# EasyEDA_SCH_alexo_2026-07-04.net
KiCad netlist of a schematic drawn in EasyEDA
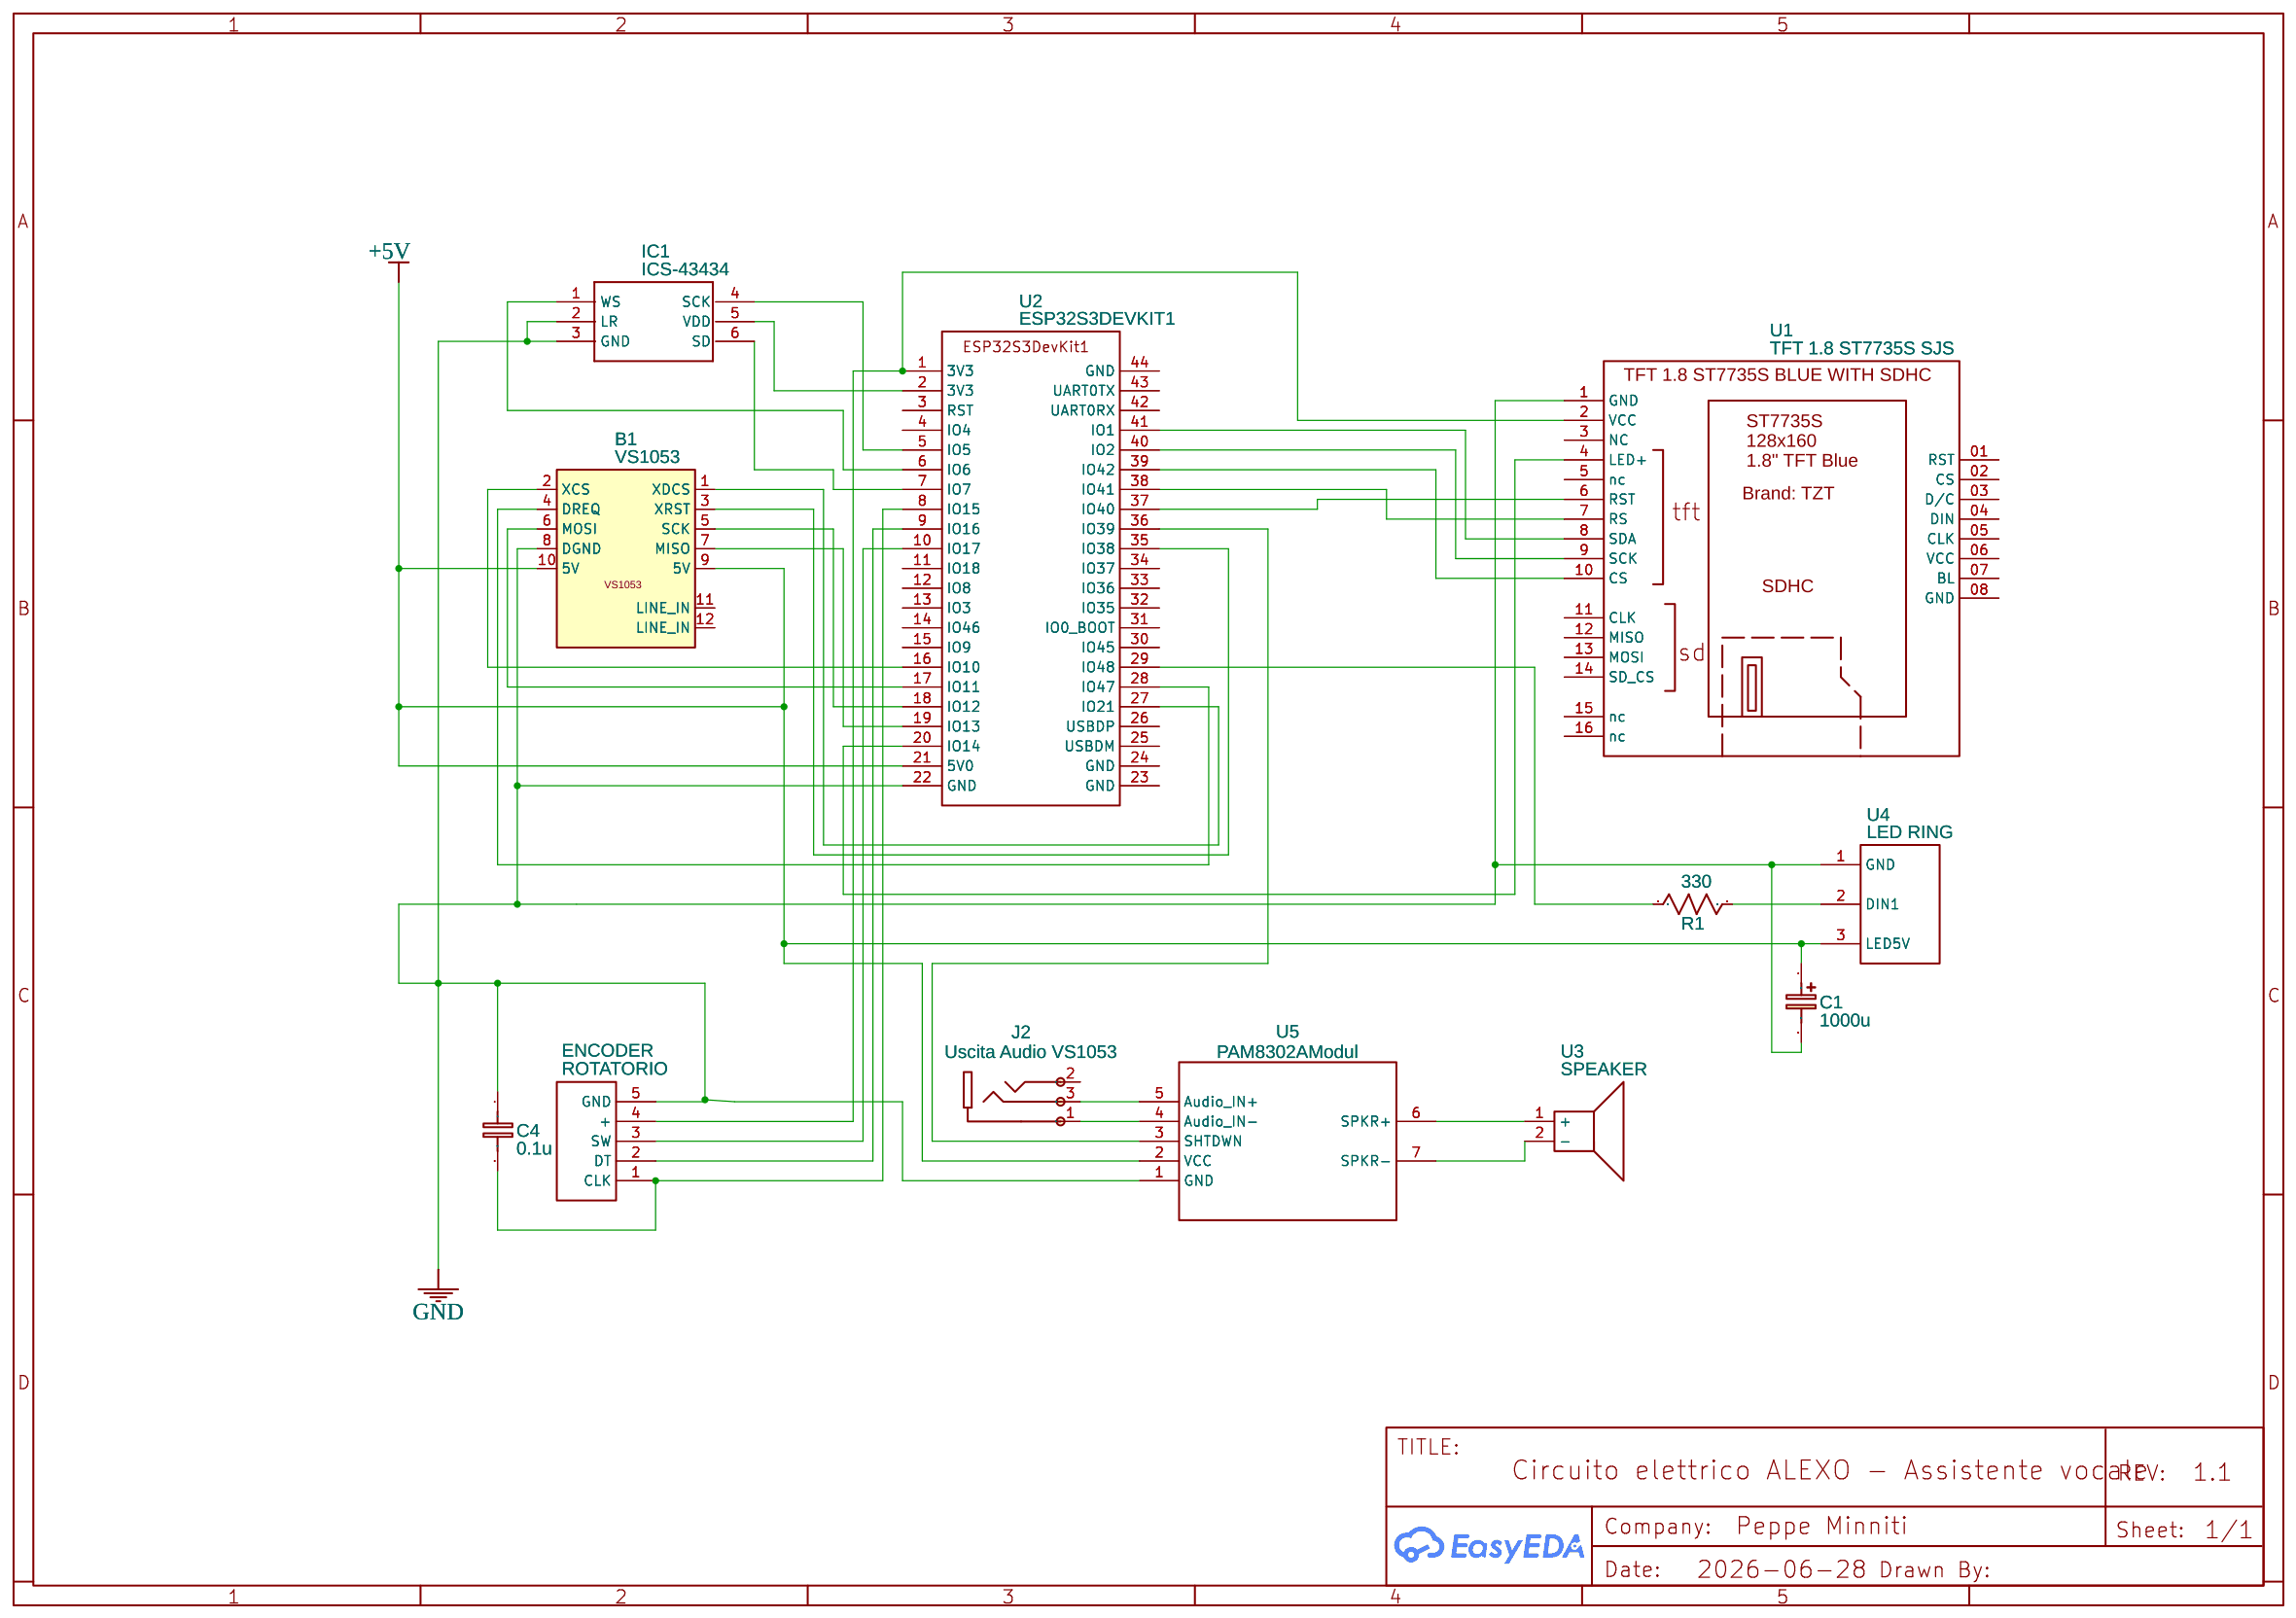
[diagram p0: schematic sheet]

(export (version "E")
  (design (tool "Eeschema 10.0.6"))
  (components
    (comp (ref "B1") (value "VS1053") (libsource (lib "") (part "VS1053")))
    (comp (ref "C1") (value "1000u") (libsource (lib "") (part "C_Tan_SMD_A_EU")))
    (comp (ref "C4") (value "0.1u") (libsource (lib "") (part "C_0603_EU")))
    (comp (ref "ENCODER") (value "ROTATORIO") (libsource (lib "") (part "ROTARY ENCODER (BREAKOUT)")))
    (comp (ref "IC1") (value "ICS-43434") (libsource (lib "") (part "ICS-43434")))
    (comp (ref "J2")
      (value "Uscita Audio VS1053")
      (fields (field (name "Manufacturer Part") "320B/PJ-0013.5Jacks"))
      (libsource (lib "") (part "320B/PJ-0013.5JACKS"))
    )
    (comp (ref "R1") (value "330") (libsource (lib "") (part "R_0603_US")))
    (comp (ref "U1") (value "TFT 1.8 ST7735S SJS") (libsource (lib "") (part "TFT 1.8 ST7735S SJS")))
    (comp (ref "U2")
      (value "ESP32S3DEVKIT1")
      (fields (field (name "Manufacturer Part") "ESP32S3DevKit1"))
      (libsource (lib "") (part "ESP32S3DEVKIT1 COPY"))
    )
    (comp (ref "U3") (value "SPEAKER") (libsource (lib "") (part "SPEAKER COPY")))
    (comp (ref "U4") (value "LED RING") (libsource (lib "") (part "LED RING")))
    (comp (ref "U5") (value "PAM8302AModul") (libsource (lib "") (part "PAM8302AModul")))
  )
  (nets
    (net (code "1") (name "+5V") (class "Default")
      (node (ref "B1") (pin "10") (pinfunction "5V_10") (pintype "bidirectional"))
      (node (ref "B1") (pin "9") (pinfunction "5V_9") (pintype "bidirectional"))
      (node (ref "C1") (pin "1") (pinfunction "1_1") (pintype "unspecified"))
      (node (ref "U2") (pin "21") (pinfunction "5V0_21") (pintype "unspecified"))
      (node (ref "U4") (pin "3") (pinfunction "LED5V_3") (pintype "unspecified"))
      (node (ref "U5") (pin "2") (pinfunction "VCC_2") (pintype "unspecified"))
    )
    (net (code "2") (name "GND") (class "Default")
      (node (ref "B1") (pin "8") (pinfunction "DGND_8") (pintype "bidirectional"))
      (node (ref "C1") (pin "2") (pinfunction "2_2") (pintype "unspecified"))
      (node (ref "C4") (pin "1") (pinfunction "1_1") (pintype "unspecified"))
      (node (ref "ENCODER") (pin "5") (pinfunction "GND_5") (pintype "unspecified"))
      (node (ref "IC1") (pin "2") (pinfunction "LR_2") (pintype "bidirectional"))
      (node (ref "IC1") (pin "3") (pinfunction "GND_3") (pintype "bidirectional"))
      (node (ref "U1") (pin "1") (pinfunction "GND_1") (pintype "unspecified"))
      (node (ref "U2") (pin "22") (pinfunction "GND_22") (pintype "unspecified"))
      (node (ref "U4") (pin "1") (pinfunction "GND_1") (pintype "unspecified"))
      (node (ref "U5") (pin "1") (pinfunction "GND_1") (pintype "unspecified"))
    )
    (net (code "3") (name "Net-(B1-DREQ)") (class "Default")
      (node (ref "B1") (pin "4") (pinfunction "DREQ_4") (pintype "bidirectional"))
      (node (ref "U2") (pin "28") (pinfunction "IO47_28") (pintype "unspecified"))
    )
    (net (code "4") (name "Net-(B1-MISO)") (class "Default")
      (node (ref "B1") (pin "7") (pinfunction "MISO_7") (pintype "bidirectional"))
      (node (ref "U2") (pin "19") (pinfunction "IO13_19") (pintype "unspecified"))
    )
    (net (code "5") (name "Net-(B1-MOSI)") (class "Default")
      (node (ref "B1") (pin "6") (pinfunction "MOSI_6") (pintype "bidirectional"))
      (node (ref "U2") (pin "17") (pinfunction "IO11_17") (pintype "unspecified"))
    )
    (net (code "6") (name "Net-(B1-SCK)") (class "Default")
      (node (ref "B1") (pin "5") (pinfunction "SCK_5") (pintype "bidirectional"))
      (node (ref "U2") (pin "18") (pinfunction "IO12_18") (pintype "unspecified"))
    )
    (net (code "7") (name "Net-(B1-XCS)") (class "Default")
      (node (ref "B1") (pin "2") (pinfunction "XCS_2") (pintype "bidirectional"))
      (node (ref "U2") (pin "16") (pinfunction "IO10_16") (pintype "unspecified"))
    )
    (net (code "8") (name "Net-(B1-XDCS)") (class "Default")
      (node (ref "B1") (pin "1") (pinfunction "XDCS_1") (pintype "bidirectional"))
      (node (ref "U2") (pin "27") (pinfunction "IO21_27") (pintype "unspecified"))
    )
    (net (code "9") (name "Net-(B1-XRST)") (class "Default")
      (node (ref "B1") (pin "3") (pinfunction "XRST_3") (pintype "bidirectional"))
      (node (ref "U2") (pin "35") (pinfunction "IO38_35") (pintype "unspecified"))
    )
    (net (code "10") (name "Net-(ENCODER-+)") (class "Default")
      (node (ref "ENCODER") (pin "4") (pinfunction "+_4") (pintype "unspecified"))
      (node (ref "U1") (pin "2") (pinfunction "VCC_2") (pintype "unspecified"))
      (node (ref "U2") (pin "1") (pinfunction "3V3_1") (pintype "unspecified"))
    )
    (net (code "11") (name "Net-(ENCODER-CLK)") (class "Default")
      (node (ref "C4") (pin "2") (pinfunction "2_2") (pintype "unspecified"))
      (node (ref "ENCODER") (pin "1") (pinfunction "CLK_1") (pintype "unspecified"))
      (node (ref "U2") (pin "8") (pinfunction "IO15_8") (pintype "unspecified"))
    )
    (net (code "12") (name "Net-(ENCODER-DT)") (class "Default")
      (node (ref "ENCODER") (pin "2") (pinfunction "DT_2") (pintype "unspecified"))
      (node (ref "U2") (pin "9") (pinfunction "IO16_9") (pintype "unspecified"))
    )
    (net (code "13") (name "Net-(ENCODER-SW)") (class "Default")
      (node (ref "ENCODER") (pin "3") (pinfunction "SW_3") (pintype "unspecified"))
      (node (ref "U2") (pin "10") (pinfunction "IO17_10") (pintype "unspecified"))
    )
    (net (code "14") (name "Net-(IC1-SCK)") (class "Default")
      (node (ref "IC1") (pin "4") (pinfunction "SCK_4") (pintype "bidirectional"))
      (node (ref "U2") (pin "5") (pinfunction "IO5_5") (pintype "unspecified"))
    )
    (net (code "15") (name "Net-(IC1-SD)") (class "Default")
      (node (ref "IC1") (pin "6") (pinfunction "SD_6") (pintype "bidirectional"))
      (node (ref "U2") (pin "7") (pinfunction "IO7_7") (pintype "unspecified"))
    )
    (net (code "16") (name "Net-(IC1-VDD)") (class "Default")
      (node (ref "IC1") (pin "5") (pinfunction "VDD_5") (pintype "bidirectional"))
      (node (ref "U2") (pin "2") (pinfunction "3V3_2") (pintype "unspecified"))
    )
    (net (code "17") (name "Net-(IC1-WS)") (class "Default")
      (node (ref "IC1") (pin "1") (pinfunction "WS_1") (pintype "bidirectional"))
      (node (ref "U2") (pin "6") (pinfunction "IO6_6") (pintype "unspecified"))
    )
    (net (code "18") (name "Net-(U1-LED+)") (class "Default")
      (node (ref "U1") (pin "4") (pinfunction "LED+_4") (pintype "unspecified"))
      (node (ref "U2") (pin "20") (pinfunction "IO14_20") (pintype "unspecified"))
    )
    (net (code "19") (name "Net-(U1-RS)") (class "Default")
      (node (ref "U1") (pin "7") (pinfunction "RS_7") (pintype "unspecified"))
      (node (ref "U2") (pin "38") (pinfunction "IO41_38") (pintype "unspecified"))
    )
    (net (code "20") (name "Net-(U1-SCK)") (class "Default")
      (node (ref "U1") (pin "9") (pinfunction "SCK_9") (pintype "unspecified"))
      (node (ref "U2") (pin "40") (pinfunction "IO2_40") (pintype "unspecified"))
    )
    (net (code "21") (name "Net-(U1-SDA)") (class "Default")
      (node (ref "U1") (pin "8") (pinfunction "SDA_8") (pintype "unspecified"))
      (node (ref "U2") (pin "41") (pinfunction "IO1_41") (pintype "unspecified"))
    )
    (net (code "22") (name "Net-(U2-IO39)") (class "Default")
      (node (ref "U2") (pin "36") (pinfunction "IO39_36") (pintype "unspecified"))
      (node (ref "U5") (pin "3") (pinfunction "SHTDWN_3") (pintype "unspecified"))
    )
    (net (code "23") (name "Net-(U2-IO40)") (class "Default")
      (node (ref "U1") (pin "6") (pinfunction "RST_6") (pintype "unspecified"))
      (node (ref "U2") (pin "37") (pinfunction "IO40_37") (pintype "unspecified"))
    )
    (net (code "24") (name "Net-(U2-IO42)") (class "Default")
      (node (ref "U1") (pin "10") (pinfunction "CS_10") (pintype "unspecified"))
      (node (ref "U2") (pin "39") (pinfunction "IO42_39") (pintype "unspecified"))
    )
    (net (code "25") (name "Net-(U2-IO48)") (class "Default")
      (node (ref "R1") (pin "1") (pinfunction "1_1") (pintype "unspecified"))
      (node (ref "U2") (pin "29") (pinfunction "IO48_29") (pintype "unspecified"))
    )
    (net (code "26") (name "Net-(U3-+)") (class "Default")
      (node (ref "U3") (pin "1") (pinfunction "+_1") (pintype "unspecified"))
      (node (ref "U5") (pin "6") (pinfunction "SPKR+_6") (pintype "unspecified"))
    )
    (net (code "27") (name "Net-(U3--)") (class "Default")
      (node (ref "U3") (pin "2") (pinfunction "-_2") (pintype "unspecified"))
      (node (ref "U5") (pin "7") (pinfunction "SPKR-_7") (pintype "unspecified"))
    )
    (net (code "28") (name "Net-(U4-DIN1)") (class "Default")
      (node (ref "R1") (pin "2") (pinfunction "2_2") (pintype "unspecified"))
      (node (ref "U4") (pin "2") (pinfunction "DIN1_2") (pintype "unspecified"))
    )
    (net (code "29") (name "Net-(U5-Audio_IN+)") (class "Default")
      (node (ref "J2") (pin "3") (pinfunction "3_3") (pintype "input"))
      (node (ref "U5") (pin "5") (pinfunction "Audio_IN+_5") (pintype "unspecified"))
    )
    (net (code "30") (name "Net-(U5-Audio_IN-)") (class "Default")
      (node (ref "J2") (pin "1") (pinfunction "1_1") (pintype "input"))
      (node (ref "U5") (pin "4") (pinfunction "Audio_IN-_4") (pintype "unspecified"))
    )
    (net (code "31") (name "unconnected-(B1-LINE_IN-Pad11)") (class "Default")
      (node (ref "B1") (pin "11") (pinfunction "LINE_IN_11") (pintype "bidirectional"))
    )
    (net (code "32") (name "unconnected-(B1-LINE_IN-Pad12)") (class "Default")
      (node (ref "B1") (pin "12") (pinfunction "LINE_IN_12") (pintype "bidirectional"))
    )
    (net (code "33") (name "unconnected-(J2-Pad2)") (class "Default")
      (node (ref "J2") (pin "2") (pinfunction "2_2") (pintype "input"))
    )
    (net (code "34") (name "unconnected-(U1-BL-Pad07)") (class "Default")
      (node (ref "U1") (pin "07") (pinfunction "BL_07") (pintype "unspecified"))
    )
    (net (code "35") (name "unconnected-(U1-CLK-Pad05)") (class "Default")
      (node (ref "U1") (pin "05") (pinfunction "CLK_05") (pintype "unspecified"))
    )
    (net (code "36") (name "unconnected-(U1-CLK-Pad11)") (class "Default")
      (node (ref "U1") (pin "11") (pinfunction "CLK_11") (pintype "unspecified"))
    )
    (net (code "37") (name "unconnected-(U1-CS-Pad02)") (class "Default")
      (node (ref "U1") (pin "02") (pinfunction "CS_02") (pintype "unspecified"))
    )
    (net (code "38") (name "unconnected-(U1-DIN-Pad04)") (class "Default")
      (node (ref "U1") (pin "04") (pinfunction "DIN_04") (pintype "unspecified"))
    )
    (net (code "39") (name "unconnected-(U1-D{slash}C-Pad03)") (class "Default")
      (node (ref "U1") (pin "03") (pinfunction "D/C_03") (pintype "unspecified"))
    )
    (net (code "40") (name "unconnected-(U1-GND-Pad08)") (class "Default")
      (node (ref "U1") (pin "08") (pinfunction "GND_08") (pintype "unspecified"))
    )
    (net (code "41") (name "unconnected-(U1-MISO-Pad12)") (class "Default")
      (node (ref "U1") (pin "12") (pinfunction "MISO_12") (pintype "unspecified"))
    )
    (net (code "42") (name "unconnected-(U1-MOSI-Pad13)") (class "Default")
      (node (ref "U1") (pin "13") (pinfunction "MOSI_13") (pintype "unspecified"))
    )
    (net (code "43") (name "unconnected-(U1-NC-Pad3)") (class "Default")
      (node (ref "U1") (pin "3") (pinfunction "NC_3") (pintype "unspecified"))
    )
    (net (code "44") (name "unconnected-(U1-RST-Pad01)") (class "Default")
      (node (ref "U1") (pin "01") (pinfunction "RST_01") (pintype "unspecified"))
    )
    (net (code "45") (name "unconnected-(U1-SD_CS-Pad14)") (class "Default")
      (node (ref "U1") (pin "14") (pinfunction "SD_CS_14") (pintype "unspecified"))
    )
    (net (code "46") (name "unconnected-(U1-VCC-Pad06)") (class "Default")
      (node (ref "U1") (pin "06") (pinfunction "VCC_06") (pintype "unspecified"))
    )
    (net (code "47") (name "unconnected-(U1-nc-Pad5)") (class "Default")
      (node (ref "U1") (pin "5") (pinfunction "nc_5") (pintype "unspecified"))
    )
    (net (code "48") (name "unconnected-(U1-nc-Pad15)") (class "Default")
      (node (ref "U1") (pin "15") (pinfunction "nc_15") (pintype "unspecified"))
    )
    (net (code "49") (name "unconnected-(U1-nc-Pad16)") (class "Default")
      (node (ref "U1") (pin "16") (pinfunction "nc_16") (pintype "unspecified"))
    )
    (net (code "50") (name "unconnected-(U2-GND-Pad23)") (class "Default")
      (node (ref "U2") (pin "23") (pinfunction "GND_23") (pintype "unspecified"))
    )
    (net (code "51") (name "unconnected-(U2-GND-Pad24)") (class "Default")
      (node (ref "U2") (pin "24") (pinfunction "GND_24") (pintype "unspecified"))
    )
    (net (code "52") (name "unconnected-(U2-GND-Pad44)") (class "Default")
      (node (ref "U2") (pin "44") (pinfunction "GND_44") (pintype "unspecified"))
    )
    (net (code "53") (name "unconnected-(U2-IO0_BOOT-Pad31)") (class "Default")
      (node (ref "U2") (pin "31") (pinfunction "IO0_BOOT_31") (pintype "unspecified"))
    )
    (net (code "54") (name "unconnected-(U2-IO3-Pad13)") (class "Default")
      (node (ref "U2") (pin "13") (pinfunction "IO3_13") (pintype "unspecified"))
    )
    (net (code "55") (name "unconnected-(U2-IO4-Pad4)") (class "Default")
      (node (ref "U2") (pin "4") (pinfunction "IO4_4") (pintype "unspecified"))
    )
    (net (code "56") (name "unconnected-(U2-IO8-Pad12)") (class "Default")
      (node (ref "U2") (pin "12") (pinfunction "IO8_12") (pintype "unspecified"))
    )
    (net (code "57") (name "unconnected-(U2-IO9-Pad15)") (class "Default")
      (node (ref "U2") (pin "15") (pinfunction "IO9_15") (pintype "unspecified"))
    )
    (net (code "58") (name "unconnected-(U2-IO18-Pad11)") (class "Default")
      (node (ref "U2") (pin "11") (pinfunction "IO18_11") (pintype "unspecified"))
    )
    (net (code "59") (name "unconnected-(U2-IO35-Pad32)") (class "Default")
      (node (ref "U2") (pin "32") (pinfunction "IO35_32") (pintype "unspecified"))
    )
    (net (code "60") (name "unconnected-(U2-IO36-Pad33)") (class "Default")
      (node (ref "U2") (pin "33") (pinfunction "IO36_33") (pintype "unspecified"))
    )
    (net (code "61") (name "unconnected-(U2-IO37-Pad34)") (class "Default")
      (node (ref "U2") (pin "34") (pinfunction "IO37_34") (pintype "unspecified"))
    )
    (net (code "62") (name "unconnected-(U2-IO45-Pad30)") (class "Default")
      (node (ref "U2") (pin "30") (pinfunction "IO45_30") (pintype "unspecified"))
    )
    (net (code "63") (name "unconnected-(U2-IO46-Pad14)") (class "Default")
      (node (ref "U2") (pin "14") (pinfunction "IO46_14") (pintype "unspecified"))
    )
    (net (code "64") (name "unconnected-(U2-RST-Pad3)") (class "Default")
      (node (ref "U2") (pin "3") (pinfunction "RST_3") (pintype "unspecified"))
    )
    (net (code "65") (name "unconnected-(U2-UART0RX-Pad42)") (class "Default")
      (node (ref "U2") (pin "42") (pinfunction "UART0RX_42") (pintype "unspecified"))
    )
    (net (code "66") (name "unconnected-(U2-UART0TX-Pad43)") (class "Default")
      (node (ref "U2") (pin "43") (pinfunction "UART0TX_43") (pintype "unspecified"))
    )
    (net (code "67") (name "unconnected-(U2-USBDM-Pad25)") (class "Default")
      (node (ref "U2") (pin "25") (pinfunction "USBDM_25") (pintype "unspecified"))
    )
    (net (code "68") (name "unconnected-(U2-USBDP-Pad26)") (class "Default")
      (node (ref "U2") (pin "26") (pinfunction "USBDP_26") (pintype "unspecified"))
    )
  )
)
